# Schematic_Alarm_clock.net
KiCad netlist of a schematic drawn in EasyEDA
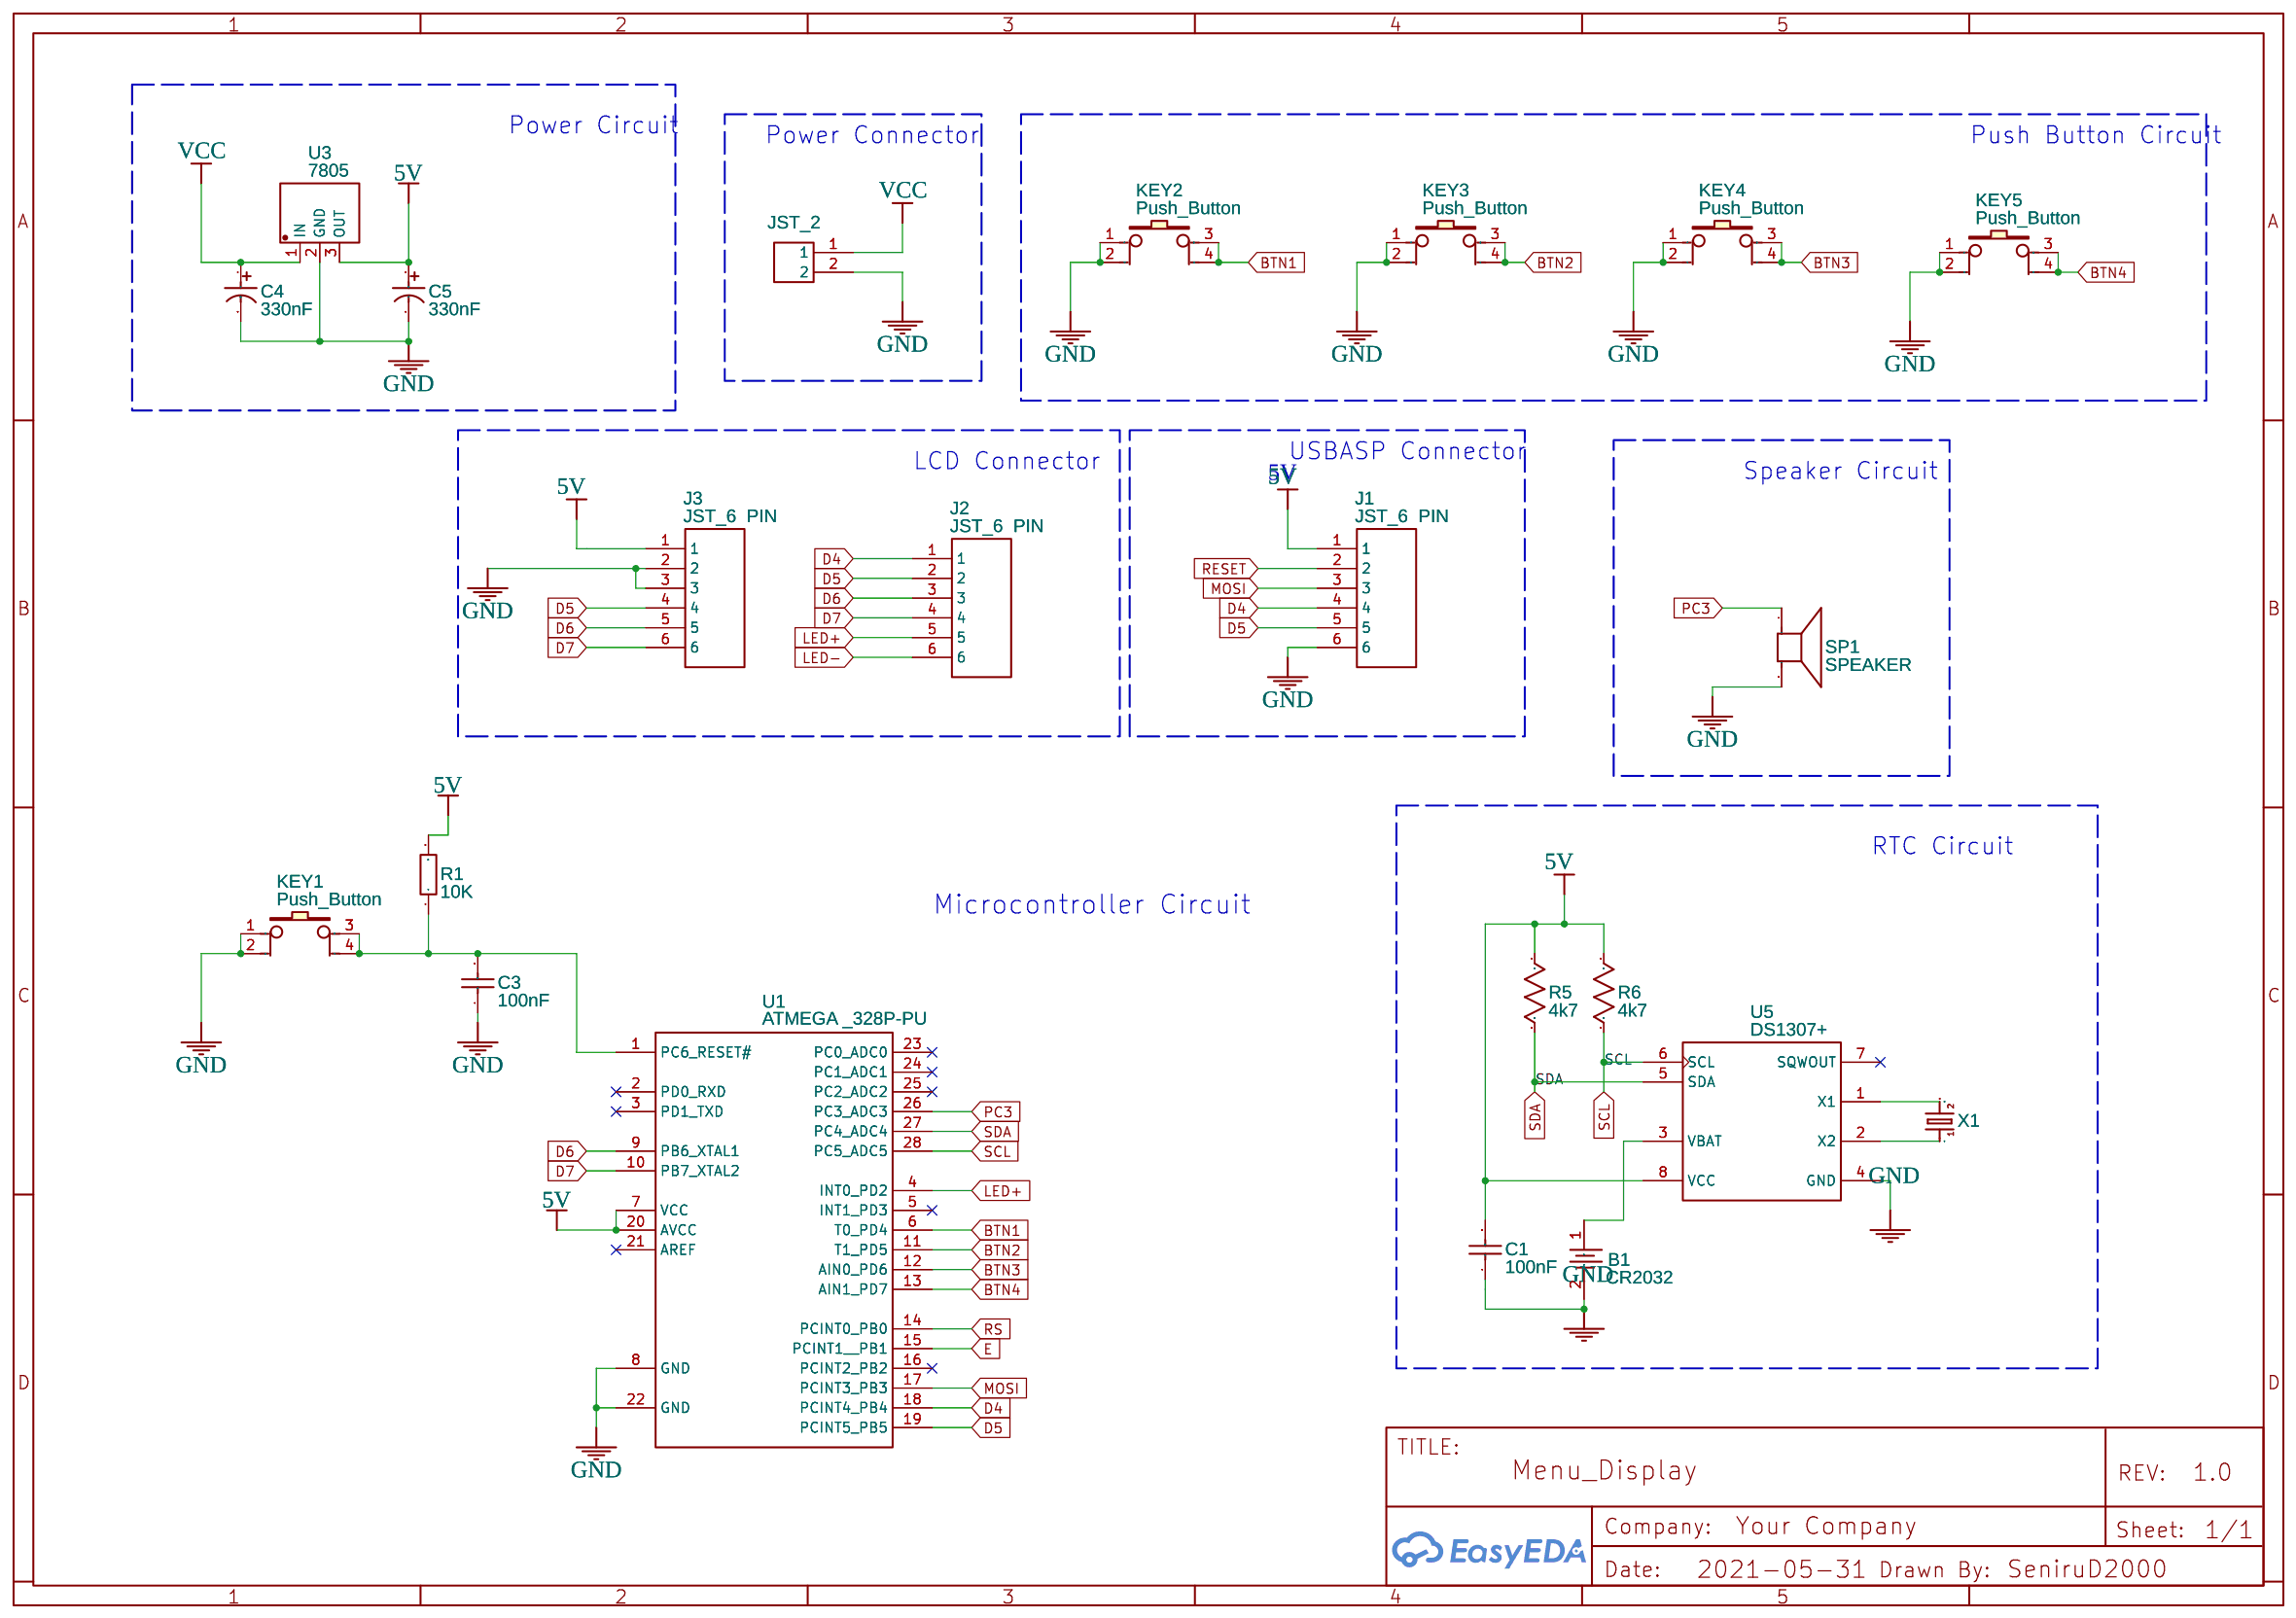
[diagram p0: schematic sheet]

(export (version "E")
  (design (tool "Eeschema 10.0.6"))
  (components
    (comp (ref "B1")
      (value "CR2032")
      (fields (field (name "BOM_Manufacturer Part") "BS-2-1") (field (name "BOM_Supplier Part") "C70376"))
      (libsource (lib "") (part "Unknown_795_-175"))
    )
    (comp (ref "C1")
      (value "100nF")
      (fields
        (field (name "BOM_Manufacturer Part") "0.1UF(104) +-20% 63v")
        (field (name "BOM_Supplier Part") "C19355")
      )
      (libsource (lib "") (part "100nF"))
    )
    (comp (ref "C3")
      (value "100nF")
      (fields
        (field (name "BOM_Manufacturer Part") "0.1UF(104) +-20% 63v")
        (field (name "BOM_Supplier Part") "C19355")
      )
      (libsource (lib "") (part "100nF"))
    )
    (comp (ref "C4")
      (value "330nF")
      (fields
        (field (name "BOM_Manufacturer Part") "0.33uF 50V 5*11")
        (field (name "BOM_Supplier Part") "C45097")
      )
      (libsource (lib "") (part "0.33uF"))
    )
    (comp (ref "C5")
      (value "330nF")
      (fields
        (field (name "BOM_Manufacturer Part") "0.33uF 50V 5*11")
        (field (name "BOM_Supplier Part") "C45097")
      )
      (libsource (lib "") (part "0.33uF"))
    )
    (comp (ref "CN1")
      (value "JST_2")
      (fields
        (field (name "BOM_Manufacturer Part") "XHB-2A Connector")
        (field (name "BOM_Supplier Part") "C57981")
      )
      (libsource (lib "") (part "JST_2 PIN"))
    )
    (comp (ref "J1") (value "JST_6  PIN") (libsource (lib "") (part "JST_6  PIN")))
    (comp (ref "J2") (value "JST_6  PIN") (libsource (lib "") (part "JST_6  PIN")))
    (comp (ref "J3") (value "JST_6  PIN") (libsource (lib "") (part "JST_6  PIN")))
    (comp (ref "KEY1")
      (value "Push_Button")
      (fields
        (field (name "BOM_Manufacturer Part") "button6*6*8.5")
        (field (name "BOM_Supplier Part") "C59980")
      )
      (libsource (lib "") (part "Push_Button"))
    )
    (comp (ref "KEY2")
      (value "Push_Button")
      (fields
        (field (name "BOM_Manufacturer Part") "button6*6*8.5")
        (field (name "BOM_Supplier Part") "C59980")
      )
      (libsource (lib "") (part "Push_Button"))
    )
    (comp (ref "KEY3")
      (value "Push_Button")
      (fields
        (field (name "BOM_Manufacturer Part") "button6*6*8.5")
        (field (name "BOM_Supplier Part") "C59980")
      )
      (libsource (lib "") (part "Push_Button"))
    )
    (comp (ref "KEY4")
      (value "Push_Button")
      (fields
        (field (name "BOM_Manufacturer Part") "button6*6*8.5")
        (field (name "BOM_Supplier Part") "C59980")
      )
      (libsource (lib "") (part "Push_Button"))
    )
    (comp (ref "KEY5")
      (value "Push_Button")
      (fields
        (field (name "BOM_Manufacturer Part") "button6*6*8.5")
        (field (name "BOM_Supplier Part") "C59980")
      )
      (libsource (lib "") (part "Push_Button"))
    )
    (comp (ref "R1")
      (value "10K")
      (fields
        (field (name "BOM_Manufacturer Part") "MFR0W4F2200A50")
        (field (name "BOM_Supplier Part") "E57439")
      )
      (libsource (lib "") (part "RESISTOR"))
    )
    (comp (ref "R5")
      (value "4k7")
      (fields (field (name "BOM_Manufacturer Part") "?"))
      (libsource (lib "") (part "Resistor_1"))
    )
    (comp (ref "R6")
      (value "4k7")
      (fields (field (name "BOM_Manufacturer Part") "?"))
      (libsource (lib "") (part "Resistor"))
    )
    (comp (ref "SP1") (value "SPEAKER") (libsource (lib "") (part "SPEAKER")))
    (comp (ref "U1")
      (value "ATMEGA _328P-PU")
      (fields
        (field (name "BOM_Manufacturer Part") "ATMEGA328P-PU")
        (field (name "BOM_Supplier Part") "C33901")
      )
      (libsource (lib "") (part "ATMEGA _328P-PU"))
    )
    (comp (ref "U3")
      (value "7805")
      (fields (field (name "BOM_Supplier Part") "C305416"))
      (libsource (lib "") (part "7805_Regulator"))
    )
    (comp (ref "U5")
      (value "DS1307+")
      (fields (field (name "BOM_Supplier Part") "C59267"))
      (libsource (lib "") (part "Unknown_885_-245"))
    )
    (comp (ref "X1")
      (value "CRYSTALTC26H_EZ")
      (fields (field (name "BOM_Manufacturer Part") "?"))
      (libsource (lib "") (part "Unknown_975_-245"))
    )
  )
  (nets
    (net (code "1") (name "5V") (class "Default")
      (node (ref "C1") (pin "2") (pinfunction "2_2") (pintype "input"))
      (node (ref "C5") (pin "1") (pinfunction "1_1") (pintype "input"))
      (node (ref "J1") (pin "1") (pinfunction "1_1") (pintype "unspecified"))
      (node (ref "J3") (pin "1") (pinfunction "1_1") (pintype "unspecified"))
      (node (ref "R1") (pin "2") (pinfunction "2_2") (pintype "input"))
      (node (ref "R5") (pin "1") (pinfunction "1_1") (pintype "unspecified"))
      (node (ref "R6") (pin "2") (pinfunction "2_2") (pintype "unspecified"))
      (node (ref "U1") (pin "20") (pinfunction "AVCC_20") (pintype "passive"))
      (node (ref "U1") (pin "7") (pinfunction "VCC_7") (pintype "passive"))
      (node (ref "U3") (pin "3") (pinfunction "OUT_3") (pintype "unspecified"))
      (node (ref "U5") (pin "8") (pinfunction "VCC_8") (pintype "passive"))
    )
    (net (code "2") (name "BTN1") (class "Default")
      (node (ref "KEY2") (pin "3") (pinfunction "3_3") (pintype "input"))
      (node (ref "KEY2") (pin "4") (pinfunction "4_4") (pintype "input"))
      (node (ref "U1") (pin "6") (pinfunction "T0_PD4_6") (pintype "bidirectional"))
    )
    (net (code "3") (name "BTN2") (class "Default")
      (node (ref "KEY3") (pin "3") (pinfunction "3_3") (pintype "input"))
      (node (ref "KEY3") (pin "4") (pinfunction "4_4") (pintype "input"))
      (node (ref "U1") (pin "11") (pinfunction "T1_PD5_11") (pintype "bidirectional"))
    )
    (net (code "4") (name "BTN3") (class "Default")
      (node (ref "KEY4") (pin "3") (pinfunction "3_3") (pintype "input"))
      (node (ref "KEY4") (pin "4") (pinfunction "4_4") (pintype "input"))
      (node (ref "U1") (pin "12") (pinfunction "AIN0_PD6_12") (pintype "bidirectional"))
    )
    (net (code "5") (name "BTN4") (class "Default")
      (node (ref "KEY5") (pin "3") (pinfunction "3_3") (pintype "input"))
      (node (ref "KEY5") (pin "4") (pinfunction "4_4") (pintype "input"))
      (node (ref "U1") (pin "13") (pinfunction "AIN1_PD7_13") (pintype "bidirectional"))
    )
    (net (code "6") (name "D4") (class "Default")
      (node (ref "J1") (pin "4") (pinfunction "4_4") (pintype "unspecified"))
      (node (ref "J2") (pin "1") (pinfunction "1_1") (pintype "unspecified"))
      (node (ref "U1") (pin "18") (pinfunction "PCINT4_PB4_18") (pintype "bidirectional"))
    )
    (net (code "7") (name "D5") (class "Default")
      (node (ref "J1") (pin "5") (pinfunction "5_5") (pintype "unspecified"))
      (node (ref "J2") (pin "2") (pinfunction "2_2") (pintype "unspecified"))
      (node (ref "J3") (pin "4") (pinfunction "4_4") (pintype "unspecified"))
      (node (ref "U1") (pin "19") (pinfunction "PCINT5_PB5_19") (pintype "bidirectional"))
    )
    (net (code "8") (name "D6") (class "Default")
      (node (ref "J2") (pin "3") (pinfunction "3_3") (pintype "unspecified"))
      (node (ref "J3") (pin "5") (pinfunction "5_5") (pintype "unspecified"))
      (node (ref "U1") (pin "9") (pinfunction "PB6_XTAL1_9") (pintype "bidirectional"))
    )
    (net (code "9") (name "D7") (class "Default")
      (node (ref "J2") (pin "4") (pinfunction "4_4") (pintype "unspecified"))
      (node (ref "J3") (pin "6") (pinfunction "6_6") (pintype "unspecified"))
      (node (ref "U1") (pin "10") (pinfunction "PB7_XTAL2_10") (pintype "bidirectional"))
    )
    (net (code "10") (name "E") (class "Default")
      (node (ref "U1") (pin "15") (pinfunction "PCINT1__PB1_15") (pintype "bidirectional"))
    )
    (net (code "11") (name "GND") (class "Default")
      (node (ref "B1") (pin "2") (pinfunction "2_2") (pintype "input"))
      (node (ref "C1") (pin "1") (pinfunction "1_1") (pintype "input"))
      (node (ref "C3") (pin "1") (pinfunction "1_1") (pintype "input"))
      (node (ref "C4") (pin "2") (pinfunction "2_2") (pintype "input"))
      (node (ref "C5") (pin "2") (pinfunction "2_2") (pintype "input"))
      (node (ref "CN1") (pin "2") (pinfunction "2_2") (pintype "unspecified"))
      (node (ref "J1") (pin "6") (pinfunction "6_6") (pintype "unspecified"))
      (node (ref "J3") (pin "2") (pinfunction "2_2") (pintype "unspecified"))
      (node (ref "J3") (pin "3") (pinfunction "3_3") (pintype "unspecified"))
      (node (ref "KEY1") (pin "1") (pinfunction "1_1") (pintype "input"))
      (node (ref "KEY1") (pin "2") (pinfunction "2_2") (pintype "input"))
      (node (ref "KEY2") (pin "1") (pinfunction "1_1") (pintype "input"))
      (node (ref "KEY2") (pin "2") (pinfunction "2_2") (pintype "input"))
      (node (ref "KEY3") (pin "1") (pinfunction "1_1") (pintype "input"))
      (node (ref "KEY3") (pin "2") (pinfunction "2_2") (pintype "input"))
      (node (ref "KEY4") (pin "1") (pinfunction "1_1") (pintype "input"))
      (node (ref "KEY4") (pin "2") (pinfunction "2_2") (pintype "input"))
      (node (ref "KEY5") (pin "1") (pinfunction "1_1") (pintype "input"))
      (node (ref "KEY5") (pin "2") (pinfunction "2_2") (pintype "input"))
      (node (ref "SP1") (pin "2") (pinfunction "-_2") (pintype "unspecified"))
      (node (ref "U1") (pin "22") (pinfunction "GND_22") (pintype "passive"))
      (node (ref "U1") (pin "8") (pinfunction "GND_8") (pintype "passive"))
      (node (ref "U3") (pin "2") (pinfunction "GND_2") (pintype "unspecified"))
      (node (ref "U5") (pin "4") (pinfunction "GND_4") (pintype "passive"))
    )
    (net (code "12") (name "LED+") (class "Default")
      (node (ref "J2") (pin "5") (pinfunction "5_5") (pintype "unspecified"))
      (node (ref "U1") (pin "4") (pinfunction "INT0_PD2_4") (pintype "bidirectional"))
    )
    (net (code "13") (name "LED-") (class "Default")
      (node (ref "J2") (pin "6") (pinfunction "6_6") (pintype "unspecified"))
    )
    (net (code "14") (name "MOSI") (class "Default")
      (node (ref "J1") (pin "3") (pinfunction "3_3") (pintype "unspecified"))
      (node (ref "U1") (pin "17") (pinfunction "PCINT3_PB3_17") (pintype "bidirectional"))
    )
    (net (code "15") (name "Net-(U1-PC6_RESET#)") (class "Default")
      (node (ref "C3") (pin "2") (pinfunction "2_2") (pintype "input"))
      (node (ref "KEY1") (pin "3") (pinfunction "3_3") (pintype "input"))
      (node (ref "KEY1") (pin "4") (pinfunction "4_4") (pintype "input"))
      (node (ref "R1") (pin "1") (pinfunction "1_1") (pintype "input"))
      (node (ref "U1") (pin "1") (pinfunction "PC6_RESET#_1") (pintype "bidirectional"))
    )
    (net (code "16") (name "Net-(U5-VBAT)") (class "Default")
      (node (ref "B1") (pin "1") (pinfunction "1_1") (pintype "input"))
      (node (ref "U5") (pin "3") (pinfunction "VBAT_3") (pintype "passive"))
    )
    (net (code "17") (name "Net-(U5-X1)") (class "Default")
      (node (ref "U5") (pin "1") (pinfunction "X1_1") (pintype "unspecified"))
      (node (ref "X1") (pin "2") (pinfunction "2_2") (pintype "unspecified"))
    )
    (net (code "18") (name "Net-(U5-X2)") (class "Default")
      (node (ref "U5") (pin "2") (pinfunction "X2_2") (pintype "unspecified"))
      (node (ref "X1") (pin "1") (pinfunction "1_1") (pintype "unspecified"))
    )
    (net (code "19") (name "PC3") (class "Default")
      (node (ref "SP1") (pin "1") (pinfunction "+_1") (pintype "unspecified"))
      (node (ref "U1") (pin "26") (pinfunction "PC3_ADC3_26") (pintype "bidirectional"))
    )
    (net (code "20") (name "RESET") (class "Default")
      (node (ref "J1") (pin "2") (pinfunction "2_2") (pintype "unspecified"))
    )
    (net (code "21") (name "RS") (class "Default")
      (node (ref "U1") (pin "14") (pinfunction "PCINT0_PB0_14") (pintype "bidirectional"))
    )
    (net (code "22") (name "SCL") (class "Default")
      (node (ref "R6") (pin "1") (pinfunction "1_1") (pintype "unspecified"))
      (node (ref "U1") (pin "28") (pinfunction "PC5_ADC5_28") (pintype "bidirectional"))
      (node (ref "U5") (pin "6") (pinfunction "SCL_6") (pintype "unspecified"))
    )
    (net (code "23") (name "SDA") (class "Default")
      (node (ref "R5") (pin "2") (pinfunction "2_2") (pintype "unspecified"))
      (node (ref "U1") (pin "27") (pinfunction "PC4_ADC4_27") (pintype "bidirectional"))
      (node (ref "U5") (pin "5") (pinfunction "SDA_5") (pintype "bidirectional"))
    )
    (net (code "24") (name "VCC") (class "Default")
      (node (ref "C4") (pin "1") (pinfunction "1_1") (pintype "input"))
      (node (ref "CN1") (pin "1") (pinfunction "1_1") (pintype "unspecified"))
      (node (ref "U3") (pin "1") (pinfunction "IN_1") (pintype "unspecified"))
    )
    (net (code "25") (name "unconnected-(U1-AREF-Pad21)") (class "Default")
      (node (ref "U1") (pin "21") (pinfunction "AREF_21") (pintype "passive+no_connect"))
    )
    (net (code "26") (name "unconnected-(U1-INT1_PD3-Pad5)") (class "Default")
      (node (ref "U1") (pin "5") (pinfunction "INT1_PD3_5") (pintype "bidirectional+no_connect"))
    )
    (net (code "27") (name "unconnected-(U1-PC0_ADC0-Pad23)") (class "Default")
      (node (ref "U1") (pin "23") (pinfunction "PC0_ADC0_23") (pintype "bidirectional+no_connect"))
    )
    (net (code "28") (name "unconnected-(U1-PC1_ADC1-Pad24)") (class "Default")
      (node (ref "U1") (pin "24") (pinfunction "PC1_ADC1_24") (pintype "bidirectional+no_connect"))
    )
    (net (code "29") (name "unconnected-(U1-PC2_ADC2-Pad25)") (class "Default")
      (node (ref "U1") (pin "25") (pinfunction "PC2_ADC2_25") (pintype "bidirectional+no_connect"))
    )
    (net (code "30") (name "unconnected-(U1-PCINT2_PB2-Pad16)") (class "Default")
      (node (ref "U1") (pin "16") (pinfunction "PCINT2_PB2_16") (pintype "bidirectional+no_connect"))
    )
    (net (code "31") (name "unconnected-(U1-PD0_RXD-Pad2)") (class "Default")
      (node (ref "U1") (pin "2") (pinfunction "PD0_RXD_2") (pintype "bidirectional+no_connect"))
    )
    (net (code "32") (name "unconnected-(U1-PD1_TXD-Pad3)") (class "Default")
      (node (ref "U1") (pin "3") (pinfunction "PD1_TXD_3") (pintype "bidirectional+no_connect"))
    )
    (net (code "33") (name "unconnected-(U5-SQWOUT-Pad7)") (class "Default")
      (node (ref "U5") (pin "7") (pinfunction "SQWOUT_7") (pintype "unspecified+no_connect"))
    )
  )
)
